# semesterprojekt.net
KiCad netlist of a schematic drawn in EAGLE
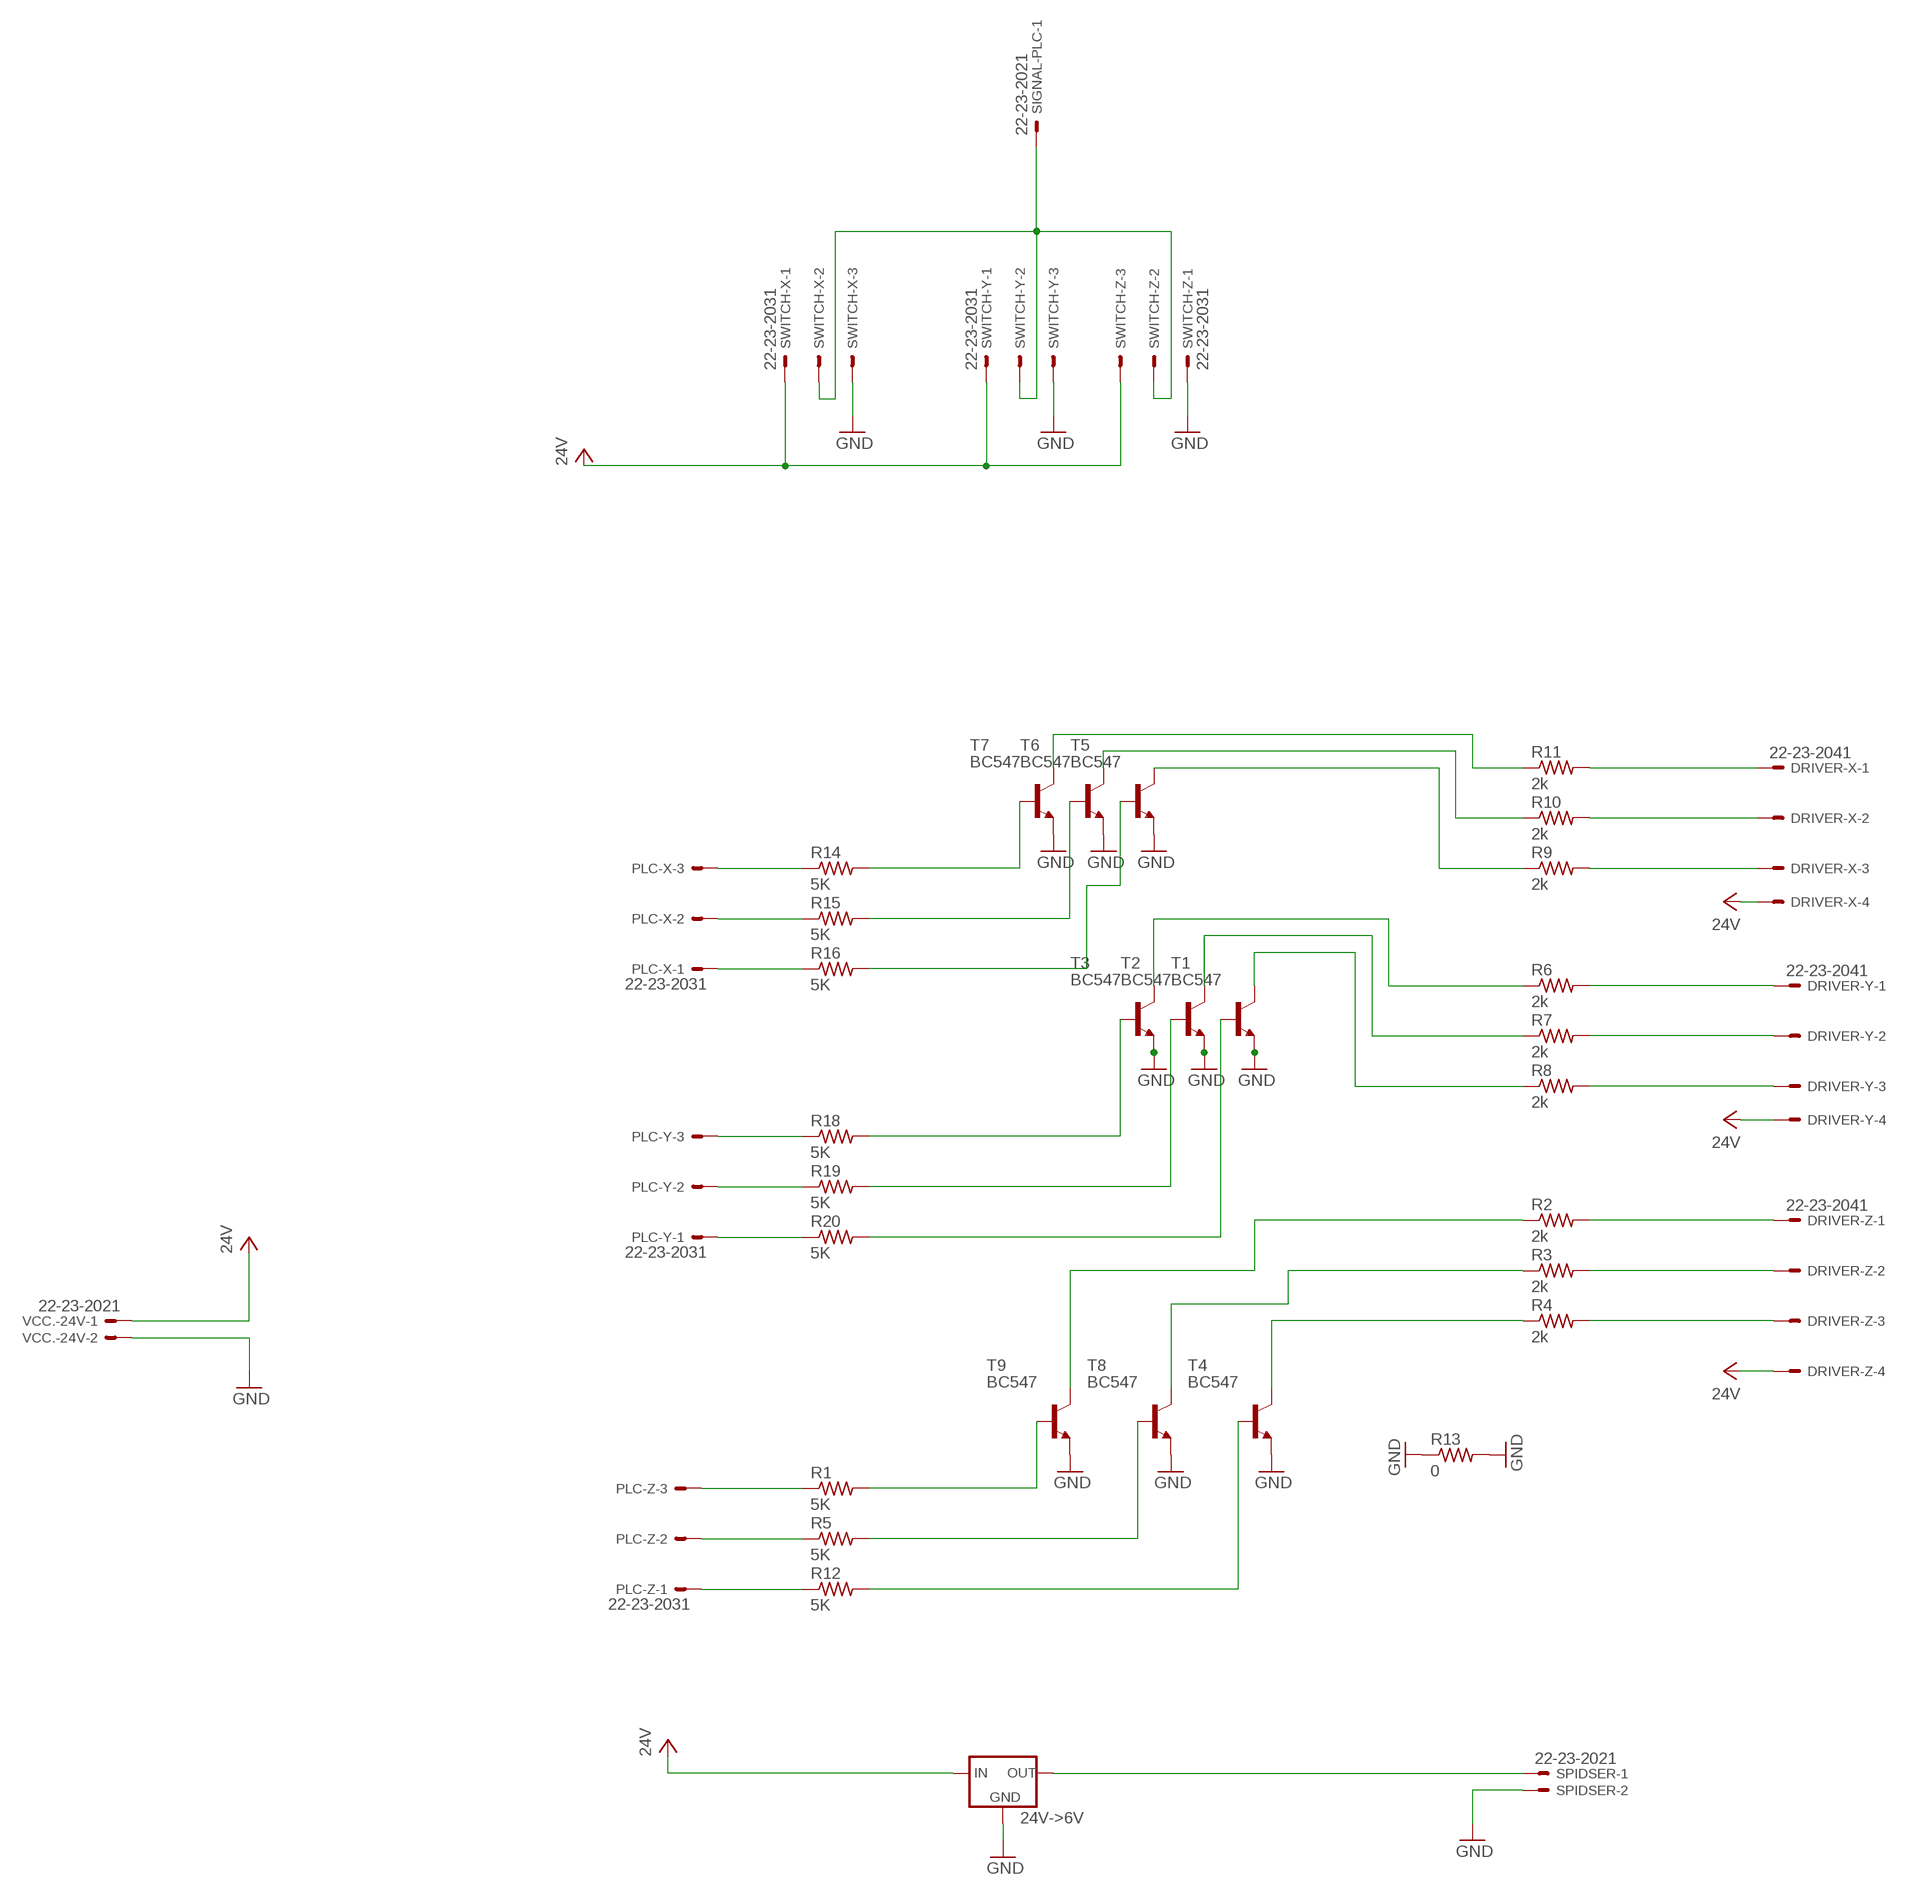
[diagram p0: schematic, sheet 1]

(export (version "E")
  (design (tool "Eeschema 10.0.6"))
  (components
    (comp (ref "24V->6V")
      (value "78XXS")
      (footprint "eagle-import:78XXS")
      (libsource (lib "eagle-import") (part "78XXS"))
    )
    (comp (ref "DRIVER-X")
      (value "22-23-2041")
      (footprint "eagle-import:22-23-2041")
      (fields (field (name "MF") "MOLEX"))
      (libsource (lib "eagle-import") (part "22-23-2041"))
    )
    (comp (ref "DRIVER-Y")
      (value "22-23-2041")
      (footprint "eagle-import:22-23-2041")
      (fields (field (name "MF") "MOLEX"))
      (libsource (lib "eagle-import") (part "22-23-2041"))
    )
    (comp (ref "DRIVER-Z")
      (value "22-23-2041")
      (footprint "eagle-import:22-23-2041")
      (fields (field (name "MF") "MOLEX"))
      (libsource (lib "eagle-import") (part "22-23-2041"))
    )
    (comp (ref "PLC-X")
      (value "22-23-2031")
      (footprint "eagle-import:22-23-2031")
      (fields (field (name "MF") "MOLEX"))
      (libsource (lib "eagle-import") (part "22-23-2031"))
    )
    (comp (ref "PLC-Y")
      (value "22-23-2031")
      (footprint "eagle-import:22-23-2031")
      (fields (field (name "MF") "MOLEX"))
      (libsource (lib "eagle-import") (part "22-23-2031"))
    )
    (comp (ref "PLC-Z")
      (value "22-23-2031")
      (footprint "eagle-import:22-23-2031")
      (fields (field (name "MF") "MOLEX"))
      (libsource (lib "eagle-import") (part "22-23-2031"))
    )
    (comp (ref "R1")
      (value "5K")
      (footprint "eagle-import:0204_7")
      (libsource (lib "eagle-import") (part "R-US_0204/7"))
    )
    (comp (ref "R2")
      (value "2k")
      (footprint "eagle-import:0204_7")
      (libsource (lib "eagle-import") (part "R-US_0204/7"))
    )
    (comp (ref "R3")
      (value "2k")
      (footprint "eagle-import:0204_7")
      (libsource (lib "eagle-import") (part "R-US_0204/7"))
    )
    (comp (ref "R4")
      (value "2k")
      (footprint "eagle-import:0204_7")
      (libsource (lib "eagle-import") (part "R-US_0204/7"))
    )
    (comp (ref "R5")
      (value "5K")
      (footprint "eagle-import:0204_7")
      (libsource (lib "eagle-import") (part "R-US_0204/7"))
    )
    (comp (ref "R6")
      (value "2k")
      (footprint "eagle-import:0204_7")
      (libsource (lib "eagle-import") (part "R-US_0204/7"))
    )
    (comp (ref "R7")
      (value "2k")
      (footprint "eagle-import:0204_7")
      (libsource (lib "eagle-import") (part "R-US_0204/7"))
    )
    (comp (ref "R8")
      (value "2k")
      (footprint "eagle-import:0204_7")
      (libsource (lib "eagle-import") (part "R-US_0204/7"))
    )
    (comp (ref "R9")
      (value "2k")
      (footprint "eagle-import:0204_7")
      (libsource (lib "eagle-import") (part "R-US_0204/7"))
    )
    (comp (ref "R10")
      (value "2k")
      (footprint "eagle-import:0204_7")
      (libsource (lib "eagle-import") (part "R-US_0204/7"))
    )
    (comp (ref "R11")
      (value "2k")
      (footprint "eagle-import:0204_7")
      (libsource (lib "eagle-import") (part "R-US_0204/7"))
    )
    (comp (ref "R12")
      (value "5K")
      (footprint "eagle-import:0204_7")
      (libsource (lib "eagle-import") (part "R-US_0204/7"))
    )
    (comp (ref "R13")
      (value "0")
      (footprint "eagle-import:0204_7")
      (libsource (lib "eagle-import") (part "R-US_0204/7"))
    )
    (comp (ref "R14")
      (value "5K")
      (footprint "eagle-import:0204_7")
      (libsource (lib "eagle-import") (part "R-US_0204/7"))
    )
    (comp (ref "R15")
      (value "5K")
      (footprint "eagle-import:0204_7")
      (libsource (lib "eagle-import") (part "R-US_0204/7"))
    )
    (comp (ref "R16")
      (value "5K")
      (footprint "eagle-import:0204_7")
      (libsource (lib "eagle-import") (part "R-US_0204/7"))
    )
    (comp (ref "R18")
      (value "5K")
      (footprint "eagle-import:0204_7")
      (libsource (lib "eagle-import") (part "R-US_0204/7"))
    )
    (comp (ref "R19")
      (value "5K")
      (footprint "eagle-import:0204_7")
      (libsource (lib "eagle-import") (part "R-US_0204/7"))
    )
    (comp (ref "R20")
      (value "5K")
      (footprint "eagle-import:0204_7")
      (libsource (lib "eagle-import") (part "R-US_0204/7"))
    )
    (comp (ref "SIGNAL-PLC")
      (value "22-23-2021")
      (footprint "eagle-import:22-23-2021")
      (fields (field (name "MF") "MOLEX"))
      (libsource (lib "eagle-import") (part "22-23-2021"))
    )
    (comp (ref "SPIDSER")
      (value "22-23-2021")
      (footprint "eagle-import:22-23-2021")
      (fields (field (name "MF") "MOLEX"))
      (libsource (lib "eagle-import") (part "22-23-2021"))
    )
    (comp (ref "SWITCH-X")
      (value "22-23-2031")
      (footprint "eagle-import:22-23-2031")
      (fields (field (name "MF") "MOLEX"))
      (libsource (lib "eagle-import") (part "22-23-2031"))
    )
    (comp (ref "SWITCH-Y")
      (value "22-23-2031")
      (footprint "eagle-import:22-23-2031")
      (fields (field (name "MF") "MOLEX"))
      (libsource (lib "eagle-import") (part "22-23-2031"))
    )
    (comp (ref "SWITCH-Z")
      (value "22-23-2031")
      (footprint "eagle-import:22-23-2031")
      (fields (field (name "MF") "MOLEX"))
      (libsource (lib "eagle-import") (part "22-23-2031"))
    )
    (comp (ref "T1")
      (value "BC547")
      (footprint "eagle-import:TO92")
      (libsource (lib "eagle-import") (part "2N3565"))
    )
    (comp (ref "T2")
      (value "BC547")
      (footprint "eagle-import:TO92")
      (libsource (lib "eagle-import") (part "2N3565"))
    )
    (comp (ref "T3")
      (value "BC547")
      (footprint "eagle-import:TO92")
      (libsource (lib "eagle-import") (part "2N3565"))
    )
    (comp (ref "T4")
      (value "BC547")
      (footprint "eagle-import:TO92")
      (libsource (lib "eagle-import") (part "2N3565"))
    )
    (comp (ref "T5")
      (value "BC547")
      (footprint "eagle-import:TO92")
      (libsource (lib "eagle-import") (part "2N3565"))
    )
    (comp (ref "T6")
      (value "BC547")
      (footprint "eagle-import:TO92")
      (libsource (lib "eagle-import") (part "2N3565"))
    )
    (comp (ref "T7")
      (value "BC547")
      (footprint "eagle-import:TO92")
      (libsource (lib "eagle-import") (part "2N3565"))
    )
    (comp (ref "T8")
      (value "BC547")
      (footprint "eagle-import:TO92")
      (libsource (lib "eagle-import") (part "2N3565"))
    )
    (comp (ref "T9")
      (value "BC547")
      (footprint "eagle-import:TO92")
      (libsource (lib "eagle-import") (part "2N3565"))
    )
    (comp (ref "VCC.-24V")
      (value "22-23-2021")
      (footprint "eagle-import:22-23-2021")
      (fields (field (name "MF") "MOLEX"))
      (libsource (lib "eagle-import") (part "22-23-2021"))
    )
  )
  (nets
    (net (code "1") (name "24V") (class "Default")
      (node (ref "24V->6V") (pin "IN") (pinfunction "IN_IN") (pintype "input"))
      (node (ref "DRIVER-X") (pin "4") (pinfunction "S_4") (pintype "passive"))
      (node (ref "DRIVER-Y") (pin "4") (pinfunction "S_4") (pintype "passive"))
      (node (ref "DRIVER-Z") (pin "4") (pinfunction "S_4") (pintype "passive"))
      (node (ref "SWITCH-X") (pin "1") (pinfunction "S_1") (pintype "passive"))
      (node (ref "SWITCH-Y") (pin "1") (pinfunction "S_1") (pintype "passive"))
      (node (ref "SWITCH-Z") (pin "3") (pinfunction "S_3") (pintype "passive"))
      (node (ref "VCC.-24V") (pin "1") (pinfunction "S_1") (pintype "passive"))
    )
    (net (code "2") (name "GND") (class "Default")
      (node (ref "24V->6V") (pin "GND") (pinfunction "GND_GND") (pintype "input"))
      (node (ref "R13") (pin "1") (pinfunction "1_1") (pintype "passive"))
      (node (ref "R13") (pin "2") (pinfunction "2_2") (pintype "passive"))
      (node (ref "SPIDSER") (pin "2") (pinfunction "S_2") (pintype "passive"))
      (node (ref "SWITCH-X") (pin "3") (pinfunction "S_3") (pintype "passive"))
      (node (ref "SWITCH-Y") (pin "3") (pinfunction "S_3") (pintype "passive"))
      (node (ref "SWITCH-Z") (pin "1") (pinfunction "S_1") (pintype "passive"))
      (node (ref "T1") (pin "3") (pinfunction "E_3") (pintype "passive"))
      (node (ref "T2") (pin "3") (pinfunction "E_3") (pintype "passive"))
      (node (ref "T3") (pin "3") (pinfunction "E_3") (pintype "passive"))
      (node (ref "T4") (pin "3") (pinfunction "E_3") (pintype "passive"))
      (node (ref "T5") (pin "3") (pinfunction "E_3") (pintype "passive"))
      (node (ref "T6") (pin "3") (pinfunction "E_3") (pintype "passive"))
      (node (ref "T7") (pin "3") (pinfunction "E_3") (pintype "passive"))
      (node (ref "T8") (pin "3") (pinfunction "E_3") (pintype "passive"))
      (node (ref "T9") (pin "3") (pinfunction "E_3") (pintype "passive"))
      (node (ref "VCC.-24V") (pin "2") (pinfunction "S_2") (pintype "passive"))
    )
    (net (code "3") (name "Net-(DRIVER-XA-S)") (class "Default")
      (node (ref "DRIVER-X") (pin "1") (pinfunction "S_1") (pintype "passive"))
      (node (ref "R11") (pin "2") (pinfunction "2_2") (pintype "passive"))
    )
    (net (code "4") (name "Net-(DRIVER-XB-S)") (class "Default")
      (node (ref "DRIVER-X") (pin "2") (pinfunction "S_2") (pintype "passive"))
      (node (ref "R10") (pin "2") (pinfunction "2_2") (pintype "passive"))
    )
    (net (code "5") (name "Net-(DRIVER-XC-S)") (class "Default")
      (node (ref "DRIVER-X") (pin "3") (pinfunction "S_3") (pintype "passive"))
      (node (ref "R9") (pin "2") (pinfunction "2_2") (pintype "passive"))
    )
    (net (code "6") (name "Net-(DRIVER-YA-S)") (class "Default")
      (node (ref "DRIVER-Y") (pin "1") (pinfunction "S_1") (pintype "passive"))
      (node (ref "R6") (pin "2") (pinfunction "2_2") (pintype "passive"))
    )
    (net (code "7") (name "Net-(DRIVER-YB-S)") (class "Default")
      (node (ref "DRIVER-Y") (pin "2") (pinfunction "S_2") (pintype "passive"))
      (node (ref "R7") (pin "2") (pinfunction "2_2") (pintype "passive"))
    )
    (net (code "8") (name "Net-(DRIVER-YC-S)") (class "Default")
      (node (ref "DRIVER-Y") (pin "3") (pinfunction "S_3") (pintype "passive"))
      (node (ref "R8") (pin "2") (pinfunction "2_2") (pintype "passive"))
    )
    (net (code "9") (name "Net-(DRIVER-ZA-S)") (class "Default")
      (node (ref "DRIVER-Z") (pin "1") (pinfunction "S_1") (pintype "passive"))
      (node (ref "R2") (pin "2") (pinfunction "2_2") (pintype "passive"))
    )
    (net (code "10") (name "Net-(DRIVER-ZB-S)") (class "Default")
      (node (ref "DRIVER-Z") (pin "2") (pinfunction "S_2") (pintype "passive"))
      (node (ref "R3") (pin "2") (pinfunction "2_2") (pintype "passive"))
    )
    (net (code "11") (name "Net-(DRIVER-ZC-S)") (class "Default")
      (node (ref "DRIVER-Z") (pin "3") (pinfunction "S_3") (pintype "passive"))
      (node (ref "R4") (pin "2") (pinfunction "2_2") (pintype "passive"))
    )
    (net (code "12") (name "Net-(PLC-XA-S)") (class "Default")
      (node (ref "PLC-X") (pin "1") (pinfunction "S_1") (pintype "passive"))
      (node (ref "R16") (pin "1") (pinfunction "1_1") (pintype "passive"))
    )
    (net (code "13") (name "Net-(PLC-XB-S)") (class "Default")
      (node (ref "PLC-X") (pin "2") (pinfunction "S_2") (pintype "passive"))
      (node (ref "R15") (pin "1") (pinfunction "1_1") (pintype "passive"))
    )
    (net (code "14") (name "Net-(PLC-XC-S)") (class "Default")
      (node (ref "PLC-X") (pin "3") (pinfunction "S_3") (pintype "passive"))
      (node (ref "R14") (pin "1") (pinfunction "1_1") (pintype "passive"))
    )
    (net (code "15") (name "Net-(PLC-YA-S)") (class "Default")
      (node (ref "PLC-Y") (pin "1") (pinfunction "S_1") (pintype "passive"))
      (node (ref "R20") (pin "1") (pinfunction "1_1") (pintype "passive"))
    )
    (net (code "16") (name "Net-(PLC-YB-S)") (class "Default")
      (node (ref "PLC-Y") (pin "2") (pinfunction "S_2") (pintype "passive"))
      (node (ref "R19") (pin "1") (pinfunction "1_1") (pintype "passive"))
    )
    (net (code "17") (name "Net-(PLC-YC-S)") (class "Default")
      (node (ref "PLC-Y") (pin "3") (pinfunction "S_3") (pintype "passive"))
      (node (ref "R18") (pin "1") (pinfunction "1_1") (pintype "passive"))
    )
    (net (code "18") (name "Net-(PLC-ZA-S)") (class "Default")
      (node (ref "PLC-Z") (pin "1") (pinfunction "S_1") (pintype "passive"))
      (node (ref "R12") (pin "1") (pinfunction "1_1") (pintype "passive"))
    )
    (net (code "19") (name "Net-(PLC-ZB-S)") (class "Default")
      (node (ref "PLC-Z") (pin "2") (pinfunction "S_2") (pintype "passive"))
      (node (ref "R5") (pin "1") (pinfunction "1_1") (pintype "passive"))
    )
    (net (code "20") (name "Net-(PLC-ZC-S)") (class "Default")
      (node (ref "PLC-Z") (pin "3") (pinfunction "S_3") (pintype "passive"))
      (node (ref "R1") (pin "1") (pinfunction "1_1") (pintype "passive"))
    )
    (net (code "21") (name "Net-(SIGNAL-PLCA-S)") (class "Default")
      (node (ref "SIGNAL-PLC") (pin "1") (pinfunction "S_1") (pintype "passive"))
      (node (ref "SWITCH-X") (pin "2") (pinfunction "S_2") (pintype "passive"))
      (node (ref "SWITCH-Y") (pin "2") (pinfunction "S_2") (pintype "passive"))
      (node (ref "SWITCH-Z") (pin "2") (pinfunction "S_2") (pintype "passive"))
    )
    (net (code "22") (name "Net-(SPIDSERA-S)") (class "Default")
      (node (ref "24V->6V") (pin "OUT") (pinfunction "OUT_OUT") (pintype "passive"))
      (node (ref "SPIDSER") (pin "1") (pinfunction "S_1") (pintype "passive"))
    )
    (net (code "23") (name "Net-(T1-B)") (class "Default")
      (node (ref "R20") (pin "2") (pinfunction "2_2") (pintype "passive"))
      (node (ref "T1") (pin "2") (pinfunction "B_2") (pintype "passive"))
    )
    (net (code "24") (name "Net-(T1-C)") (class "Default")
      (node (ref "R8") (pin "1") (pinfunction "1_1") (pintype "passive"))
      (node (ref "T1") (pin "1") (pinfunction "C_1") (pintype "passive"))
    )
    (net (code "25") (name "Net-(T2-B)") (class "Default")
      (node (ref "R19") (pin "2") (pinfunction "2_2") (pintype "passive"))
      (node (ref "T2") (pin "2") (pinfunction "B_2") (pintype "passive"))
    )
    (net (code "26") (name "Net-(T2-C)") (class "Default")
      (node (ref "R7") (pin "1") (pinfunction "1_1") (pintype "passive"))
      (node (ref "T2") (pin "1") (pinfunction "C_1") (pintype "passive"))
    )
    (net (code "27") (name "Net-(T3-B)") (class "Default")
      (node (ref "R18") (pin "2") (pinfunction "2_2") (pintype "passive"))
      (node (ref "T3") (pin "2") (pinfunction "B_2") (pintype "passive"))
    )
    (net (code "28") (name "Net-(T3-C)") (class "Default")
      (node (ref "R6") (pin "1") (pinfunction "1_1") (pintype "passive"))
      (node (ref "T3") (pin "1") (pinfunction "C_1") (pintype "passive"))
    )
    (net (code "29") (name "Net-(T4-B)") (class "Default")
      (node (ref "R12") (pin "2") (pinfunction "2_2") (pintype "passive"))
      (node (ref "T4") (pin "2") (pinfunction "B_2") (pintype "passive"))
    )
    (net (code "30") (name "Net-(T4-C)") (class "Default")
      (node (ref "R4") (pin "1") (pinfunction "1_1") (pintype "passive"))
      (node (ref "T4") (pin "1") (pinfunction "C_1") (pintype "passive"))
    )
    (net (code "31") (name "Net-(T5-B)") (class "Default")
      (node (ref "R16") (pin "2") (pinfunction "2_2") (pintype "passive"))
      (node (ref "T5") (pin "2") (pinfunction "B_2") (pintype "passive"))
    )
    (net (code "32") (name "Net-(T5-C)") (class "Default")
      (node (ref "R9") (pin "1") (pinfunction "1_1") (pintype "passive"))
      (node (ref "T5") (pin "1") (pinfunction "C_1") (pintype "passive"))
    )
    (net (code "33") (name "Net-(T6-B)") (class "Default")
      (node (ref "R15") (pin "2") (pinfunction "2_2") (pintype "passive"))
      (node (ref "T6") (pin "2") (pinfunction "B_2") (pintype "passive"))
    )
    (net (code "34") (name "Net-(T6-C)") (class "Default")
      (node (ref "R10") (pin "1") (pinfunction "1_1") (pintype "passive"))
      (node (ref "T6") (pin "1") (pinfunction "C_1") (pintype "passive"))
    )
    (net (code "35") (name "Net-(T7-B)") (class "Default")
      (node (ref "R14") (pin "2") (pinfunction "2_2") (pintype "passive"))
      (node (ref "T7") (pin "2") (pinfunction "B_2") (pintype "passive"))
    )
    (net (code "36") (name "Net-(T7-C)") (class "Default")
      (node (ref "R11") (pin "1") (pinfunction "1_1") (pintype "passive"))
      (node (ref "T7") (pin "1") (pinfunction "C_1") (pintype "passive"))
    )
    (net (code "37") (name "Net-(T8-B)") (class "Default")
      (node (ref "R5") (pin "2") (pinfunction "2_2") (pintype "passive"))
      (node (ref "T8") (pin "2") (pinfunction "B_2") (pintype "passive"))
    )
    (net (code "38") (name "Net-(T8-C)") (class "Default")
      (node (ref "R3") (pin "1") (pinfunction "1_1") (pintype "passive"))
      (node (ref "T8") (pin "1") (pinfunction "C_1") (pintype "passive"))
    )
    (net (code "39") (name "Net-(T9-B)") (class "Default")
      (node (ref "R1") (pin "2") (pinfunction "2_2") (pintype "passive"))
      (node (ref "T9") (pin "2") (pinfunction "B_2") (pintype "passive"))
    )
    (net (code "40") (name "Net-(T9-C)") (class "Default")
      (node (ref "R2") (pin "1") (pinfunction "1_1") (pintype "passive"))
      (node (ref "T9") (pin "1") (pinfunction "C_1") (pintype "passive"))
    )
  )
)
